# Circuit_DevBoard.net
KiCad netlist of a schematic drawn in EAGLE
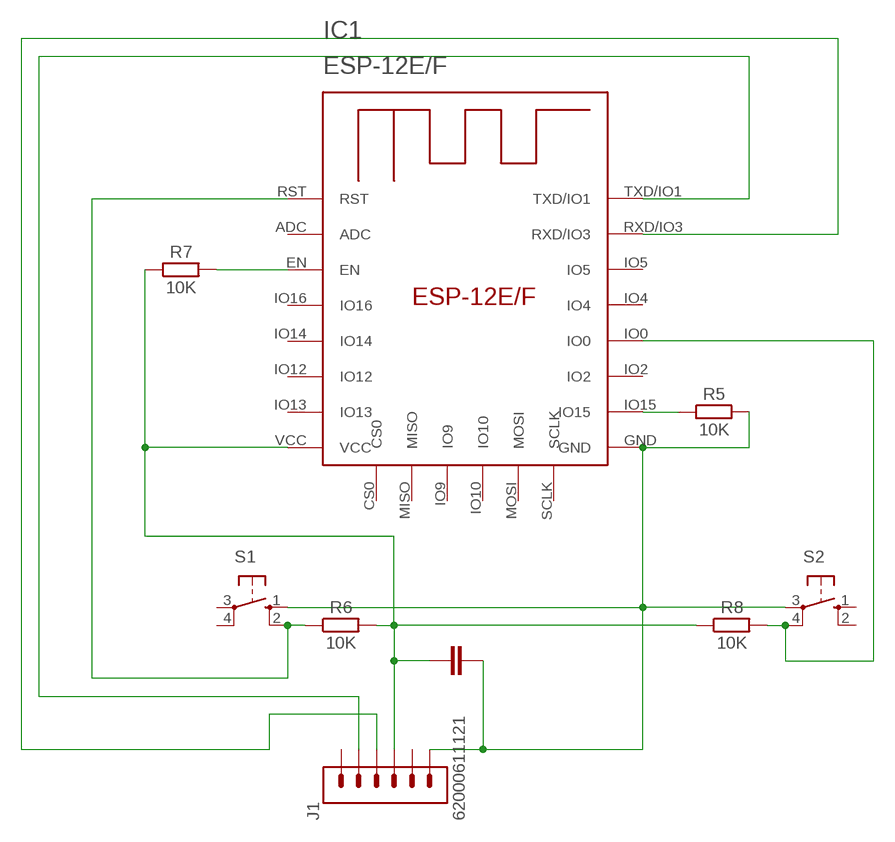
[diagram p0: schematic, sheet 1]

(export (version "E")
  (design (tool "Eeschema 10.0.6"))
  (components
    (comp (ref "IC1")
      (value "ESP-12E/F")
      (footprint "eagle-import:ESP-12E")
      (libsource (lib "eagle-import") (part "ESP-12E/F"))
    )
    (comp (ref "J1")
      (value "62000611121")
      (footprint "eagle-import:62000611121")
      (fields (field (name "MANUFACTURER") "Würth Elektronik ") (field (name "CREATED_BY") "PCBLayout.com"))
      (libsource (lib "eagle-import") (part "62000611121"))
    )
    (comp (ref "R5")
      (value "10K")
      (footprint "eagle-import:RESAD724W46L381D178B")
      (libsource (lib "eagle-import") (part "RAXIAL-7.2MM-PITCH_"))
    )
    (comp (ref "R6")
      (value "10K")
      (footprint "eagle-import:RESAD724W46L381D178B")
      (libsource (lib "eagle-import") (part "RAXIAL-7.2MM-PITCH_"))
    )
    (comp (ref "R7")
      (value "10K")
      (footprint "eagle-import:RESAD724W46L381D178B")
      (libsource (lib "eagle-import") (part "RAXIAL-7.2MM-PITCH_"))
    )
    (comp (ref "R8")
      (value "10K")
      (footprint "eagle-import:RESAD724W46L381D178B")
      (libsource (lib "eagle-import") (part "RAXIAL-7.2MM-PITCH_"))
    )
    (comp (ref "S1")
      (value "10-XX")
      (footprint "eagle-import:B3F-10XX")
      (fields (field (name "MPN") "B3F-1000"))
      (libsource (lib "eagle-import") (part "10-XX"))
    )
    (comp (ref "S2")
      (value "10-XX")
      (footprint "eagle-import:B3F-10XX")
      (fields (field (name "MPN") "B3F-1000"))
      (libsource (lib "eagle-import") (part "10-XX"))
    )
  )
  (nets
    (net (code "1") (name "Net-(IC1-PadEN)") (class "Default")
      (node (ref "IC1") (pin "EN") (pinfunction "EN_EN") (pintype "bidirectional"))
      (node (ref "R7") (pin "2") (pinfunction "2_2") (pintype "passive"))
    )
    (net (code "2") (name "Net-(IC1-PadIO15)") (class "Default")
      (node (ref "IC1") (pin "IO15") (pinfunction "IO15_IO15") (pintype "bidirectional"))
      (node (ref "R5") (pin "1") (pinfunction "1_1") (pintype "passive"))
    )
    (net (code "3") (name "Net-(IC1-PadRXD{slash}IO3)") (class "Default")
      (node (ref "IC1") (pin "RXD/IO3") (pinfunction "RXD/IO3_RXD/IO3") (pintype "bidirectional"))
      (node (ref "J1") (pin "3") (pinfunction "3_3") (pintype "passive"))
    )
    (net (code "4") (name "Net-(IC1-PadTXD{slash}IO1)") (class "Default")
      (node (ref "IC1") (pin "TXD/IO1") (pinfunction "TXD/IO1_TXD/IO1") (pintype "bidirectional"))
      (node (ref "J1") (pin "2") (pinfunction "2_2") (pintype "passive"))
    )
    (net (code "5") (name "Net-(IC1-PadVCC)") (class "Default")
      (node (ref "IC1") (pin "VCC") (pinfunction "VCC_VCC") (pintype "power_in"))
      (node (ref "J1") (pin "4") (pinfunction "4_4") (pintype "passive"))
      (node (ref "R6") (pin "2") (pinfunction "2_2") (pintype "passive"))
      (node (ref "R7") (pin "1") (pinfunction "1_1") (pintype "passive"))
      (node (ref "R8") (pin "1") (pinfunction "1_1") (pintype "passive"))
    )
    (net (code "6") (name "Net-(S1-S)") (class "Default")
      (node (ref "IC1") (pin "GND") (pinfunction "GND_GND") (pintype "power_in"))
      (node (ref "J1") (pin "6") (pinfunction "6_6") (pintype "passive"))
      (node (ref "R5") (pin "2") (pinfunction "2_2") (pintype "passive"))
      (node (ref "S1") (pin "1") (pinfunction "S_1") (pintype "passive"))
      (node (ref "S2") (pin "3") (pinfunction "P_3") (pintype "passive"))
    )
    (net (code "7") (name "Net-(S1-S1)") (class "Default")
      (node (ref "IC1") (pin "RST") (pinfunction "RST_RST") (pintype "input"))
      (node (ref "R6") (pin "1") (pinfunction "1_1") (pintype "passive"))
      (node (ref "S1") (pin "2") (pinfunction "S1_2") (pintype "passive"))
    )
    (net (code "8") (name "Net-(S2-P1)") (class "Default")
      (node (ref "IC1") (pin "IO0") (pinfunction "IO0_IO0") (pintype "bidirectional"))
      (node (ref "R8") (pin "2") (pinfunction "2_2") (pintype "passive"))
      (node (ref "S2") (pin "4") (pinfunction "P1_4") (pintype "passive"))
    )
    (net (code "9") (name "unconnected-(IC1-PadADC)") (class "Default")
      (node (ref "IC1") (pin "ADC") (pinfunction "ADC_ADC") (pintype "bidirectional"))
    )
    (net (code "10") (name "unconnected-(IC1-PadCS0)") (class "Default")
      (node (ref "IC1") (pin "CS0") (pinfunction "CS0_CS0") (pintype "bidirectional"))
    )
    (net (code "11") (name "unconnected-(IC1-PadIO2)") (class "Default")
      (node (ref "IC1") (pin "IO2") (pinfunction "IO2_IO2") (pintype "bidirectional"))
    )
    (net (code "12") (name "unconnected-(IC1-PadIO4)") (class "Default")
      (node (ref "IC1") (pin "IO4") (pinfunction "IO4_IO4") (pintype "bidirectional"))
    )
    (net (code "13") (name "unconnected-(IC1-PadIO5)") (class "Default")
      (node (ref "IC1") (pin "IO5") (pinfunction "IO5_IO5") (pintype "bidirectional"))
    )
    (net (code "14") (name "unconnected-(IC1-PadIO9)") (class "Default")
      (node (ref "IC1") (pin "IO9") (pinfunction "IO9_IO9") (pintype "bidirectional"))
    )
    (net (code "15") (name "unconnected-(IC1-PadIO10)") (class "Default")
      (node (ref "IC1") (pin "IO10") (pinfunction "IO10_IO10") (pintype "bidirectional"))
    )
    (net (code "16") (name "unconnected-(IC1-PadIO12)") (class "Default")
      (node (ref "IC1") (pin "IO12") (pinfunction "IO12_IO12") (pintype "bidirectional"))
    )
    (net (code "17") (name "unconnected-(IC1-PadIO13)") (class "Default")
      (node (ref "IC1") (pin "IO13") (pinfunction "IO13_IO13") (pintype "bidirectional"))
    )
    (net (code "18") (name "unconnected-(IC1-PadIO14)") (class "Default")
      (node (ref "IC1") (pin "IO14") (pinfunction "IO14_IO14") (pintype "bidirectional"))
    )
    (net (code "19") (name "unconnected-(IC1-PadIO16)") (class "Default")
      (node (ref "IC1") (pin "IO16") (pinfunction "IO16_IO16") (pintype "bidirectional"))
    )
    (net (code "20") (name "unconnected-(IC1-PadMISO)") (class "Default")
      (node (ref "IC1") (pin "MISO") (pinfunction "MISO_MISO") (pintype "bidirectional"))
    )
    (net (code "21") (name "unconnected-(IC1-PadMOSI)") (class "Default")
      (node (ref "IC1") (pin "MOSI") (pinfunction "MOSI_MOSI") (pintype "bidirectional"))
    )
    (net (code "22") (name "unconnected-(IC1-PadSCLK)") (class "Default")
      (node (ref "IC1") (pin "SCLK") (pinfunction "SCLK_SCLK") (pintype "bidirectional"))
    )
    (net (code "23") (name "unconnected-(J1-Pad1)") (class "Default")
      (node (ref "J1") (pin "1") (pinfunction "1_1") (pintype "passive"))
    )
    (net (code "24") (name "unconnected-(J1-Pad5)") (class "Default")
      (node (ref "J1") (pin "5") (pinfunction "5_5") (pintype "passive"))
    )
    (net (code "25") (name "unconnected-(S1-P-Pad3)") (class "Default")
      (node (ref "S1") (pin "3") (pinfunction "P_3") (pintype "passive"))
    )
    (net (code "26") (name "unconnected-(S1-P1-Pad4)") (class "Default")
      (node (ref "S1") (pin "4") (pinfunction "P1_4") (pintype "passive"))
    )
    (net (code "27") (name "unconnected-(S2-S-Pad1)") (class "Default")
      (node (ref "S2") (pin "1") (pinfunction "S_1") (pintype "passive"))
    )
    (net (code "28") (name "unconnected-(S2-S1-Pad2)") (class "Default")
      (node (ref "S2") (pin "2") (pinfunction "S1_2") (pintype "passive"))
    )
  )
)
